# 03_Display.net
KiCad netlist of a schematic drawn in Altium Designer
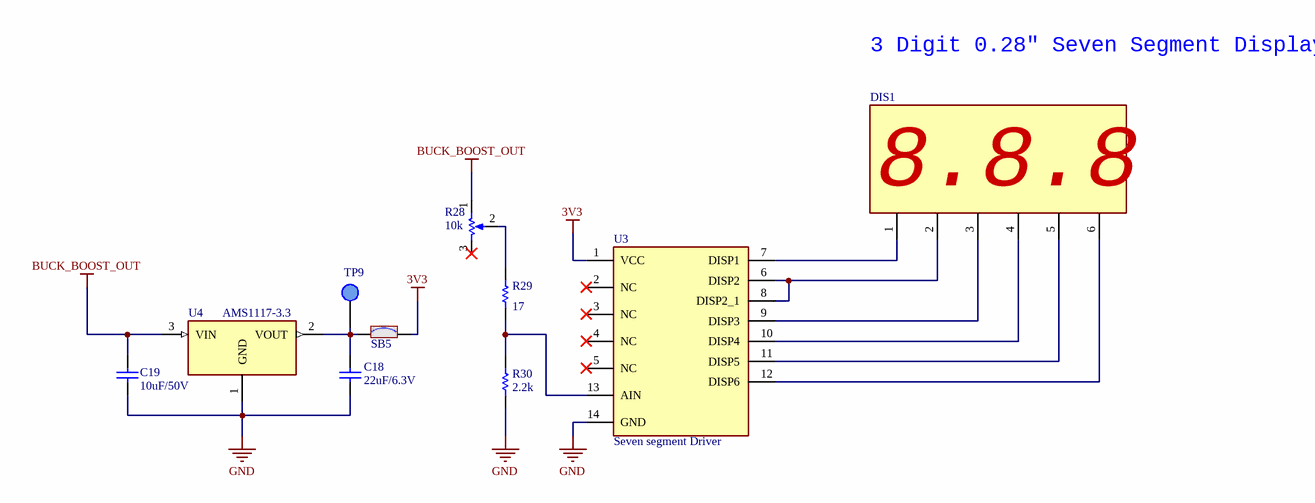
[diagram p0: 03.Display.SchDoc]

(export (version "E")
  (design (tool "Eeschema 10.0.6"))
  (components
    (comp (ref "C18")
      (value "22uF/6.3V")
      (footprint "cap0805")
      (description "Multilayer Ceramic Capacitors MLCC - SMD/SMT 6.3V 22uF X5R 0805 20 %")
      (fields (field (name "MF") "TAIYO YUDEN") (field (name "MP") "JMK212BJ226MG-T"))
      (libsource (lib "Altium_Main_Library") (part "Cap"))
    )
    (comp (ref "C19")
      (value "10uF/50V")
      (footprint "cap0805")
      (description "Multilayer Ceramic Capacitors MLCC - SMD/SMT 10 uF 50 VDC 10% 0805 X5R")
      (fields (field (name "MF") "Murata Electronics") (field (name "MP") "GRM21BR61H106KE43L"))
      (libsource (lib "Altium_Main_Library") (part "Cap"))
    )
    (comp (ref "DIS1")
      (value "6pin 3 digit seven segment display module")
      (footprint "7Segment-0.28inch")
      (libsource (lib "DC2DC_Buck_Boost_Converter_SchLib") (part "SevenSegment6Pin"))
    )
    (comp (ref "R28")
      (value "10k")
      (footprint "TRIM_TC33X-2-201G")
      (description "Potentiometer")
      (libsource (lib "DC2DC_Buck_Boost_Converter_SchLib") (part "RPot"))
    )
    (comp (ref "R29")
      (value "17")
      (footprint "RES0805")
      (description "Thick Film Resistors - SMD 17.4OHM 1/10WATT 1%")
      (fields (field (name "MP") "CR0603-FX-17R4ELF") (field (name "MF") "Bourns"))
      (libsource (lib "Altium_Main_Library") (part "Res"))
    )
    (comp (ref "R30")
      (value "2.2k")
      (footprint "RES0805")
      (description "Thin Film Resistors - SMD 2.2K ohm 1% 50 ppm Thin Film")
      (fields (field (name "MP") "RT0805FRE132K2L") (field (name "MF") "YAGEO"))
      (libsource (lib "Altium_Main_Library") (part "Res"))
    )
    (comp (ref "SB5")
      (value "SB_ON")
      (footprint "SOLDER-BRIDGE_R0805-0R")
      (description "Solder Bridge ON")
      (fields (field (name "MP") "CR0805AJ/-000EAS") (field (name "MF") "Bourns"))
      (libsource (lib "Altium_Main_Library") (part "SB_ON"))
    )
    (comp (ref "TP9")
      (value "~")
      (footprint "tp")
      (description "Test Point")
      (libsource (lib "Altium_Main_Library") (part "TP"))
    )
    (comp (ref "U3")
      (value "Seven segment Driver")
      (footprint "SOIC127P600X175-14N")
      (description "ADC/MUX/Binary2BCD/BCDto7Segment")
      (fields (field (name "MF") "ABLIC") (field (name "MP") "S-8254AAEFT-TB-G"))
      (libsource (lib "DC2DC_Buck_Boost_Converter_SchLib") (part "Seven segment Driver"))
    )
    (comp (ref "U4")
      (value "AMS1117-3.3")
      (footprint "SOT229P700X180-4N")
      (description "LDO Voltage Regulators 800MA LDO LINEAR REG")
      (fields (field (name "MF") "Texas Instruments") (field (name "MP") "LM1117MPX-3.3/NOPB"))
      (libsource (lib "DC2DC_Buck_Boost_Converter_SchLib") (part "AMS1117-3.3"))
    )
  )
  (nets
    (net (code "1") (name "3V3") (class "Default")
      (node (ref "SB5") (pin "2") (pinfunction "2_2") (pintype "passive"))
      (node (ref "U3") (pin "1") (pinfunction "VCC_1") (pintype "power_in"))
    )
    (net (code "2") (name "BUCK_BOOST_OUT") (class "Default")
      (node (ref "C19") (pin "1") (pinfunction "1_1") (pintype "passive"))
      (node (ref "R28") (pin "1") (pinfunction "TOP_1") (pintype "passive"))
      (node (ref "U4") (pin "3") (pinfunction "VIN_3") (pintype "input"))
    )
    (net (code "3") (name "GND") (class "Default")
      (node (ref "C18") (pin "2") (pinfunction "2_2") (pintype "passive"))
      (node (ref "C19") (pin "2") (pinfunction "2_2") (pintype "passive"))
      (node (ref "R30") (pin "1") (pinfunction "1_1") (pintype "passive"))
      (node (ref "U3") (pin "14") (pinfunction "GND_14") (pintype "power_in"))
      (node (ref "U4") (pin "1") (pinfunction "GND_1") (pintype "power_in"))
    )
    (net (code "4") (name "Net-(R28-TAP)") (class "Default")
      (node (ref "R28") (pin "2") (pinfunction "TAP_2") (pintype "passive"))
      (node (ref "R29") (pin "2") (pinfunction "2_2") (pintype "passive"))
    )
    (net (code "5") (name "Net-(TP9-___TP)") (class "Default")
      (node (ref "C18") (pin "1") (pinfunction "1_1") (pintype "passive"))
      (node (ref "SB5") (pin "1") (pinfunction "1_1") (pintype "passive"))
      (node (ref "TP9") (pin "1") (pinfunction "___TP_1") (pintype "passive"))
      (node (ref "U4") (pin "2") (pinfunction "VOUT_2") (pintype "output"))
    )
    (net (code "6") (name "Net-(U3-AIN)") (class "Default")
      (node (ref "R29") (pin "1") (pinfunction "1_1") (pintype "passive"))
      (node (ref "R30") (pin "2") (pinfunction "2_2") (pintype "passive"))
      (node (ref "U3") (pin "13") (pinfunction "AIN_13") (pintype "passive"))
    )
    (net (code "7") (name "Net-(U3-DISP1)") (class "Default")
      (node (ref "DIS1") (pin "1") (pintype "passive"))
      (node (ref "U3") (pin "7") (pinfunction "DISP1_7") (pintype "power_in"))
    )
    (net (code "8") (name "Net-(U3-DISP2)") (class "Default")
      (node (ref "DIS1") (pin "2") (pintype "passive"))
      (node (ref "U3") (pin "6") (pinfunction "DISP2_6") (pintype "power_in"))
      (node (ref "U3") (pin "8") (pinfunction "DISP2_1_8") (pintype "power_in"))
    )
    (net (code "9") (name "Net-(U3-DISP3)") (class "Default")
      (node (ref "DIS1") (pin "3") (pintype "passive"))
      (node (ref "U3") (pin "9") (pinfunction "DISP3_9") (pintype "passive"))
    )
    (net (code "10") (name "Net-(U3-DISP4)") (class "Default")
      (node (ref "DIS1") (pin "4") (pintype "passive"))
      (node (ref "U3") (pin "10") (pinfunction "DISP4_10") (pintype "passive"))
    )
    (net (code "11") (name "Net-(U3-DISP5)") (class "Default")
      (node (ref "DIS1") (pin "5") (pintype "passive"))
      (node (ref "U3") (pin "11") (pinfunction "DISP5_11") (pintype "passive"))
    )
    (net (code "12") (name "Net-(U3-DISP6)") (class "Default")
      (node (ref "DIS1") (pin "6") (pintype "passive"))
      (node (ref "U3") (pin "12") (pinfunction "DISP6_12") (pintype "passive"))
    )
    (net (code "13") (name "unconnected-(R28-BOT-Pad3)") (class "Default")
      (node (ref "R28") (pin "3") (pinfunction "BOT_3") (pintype "passive+no_connect"))
    )
    (net (code "14") (name "unconnected-(U3-NC-Pad2)") (class "Default")
      (node (ref "U3") (pin "2") (pinfunction "NC_2") (pintype "passive+no_connect"))
    )
    (net (code "15") (name "unconnected-(U3-NC-Pad3)") (class "Default")
      (node (ref "U3") (pin "3") (pinfunction "NC_3") (pintype "passive+no_connect"))
    )
    (net (code "16") (name "unconnected-(U3-NC-Pad4)") (class "Default")
      (node (ref "U3") (pin "4") (pinfunction "NC_4") (pintype "passive+no_connect"))
    )
    (net (code "17") (name "unconnected-(U3-NC-Pad5)") (class "Default")
      (node (ref "U3") (pin "5") (pinfunction "NC_5") (pintype "passive+no_connect"))
    )
  )
)
